# Schematic_traffic.net
KiCad netlist of a schematic drawn in Altium Designer
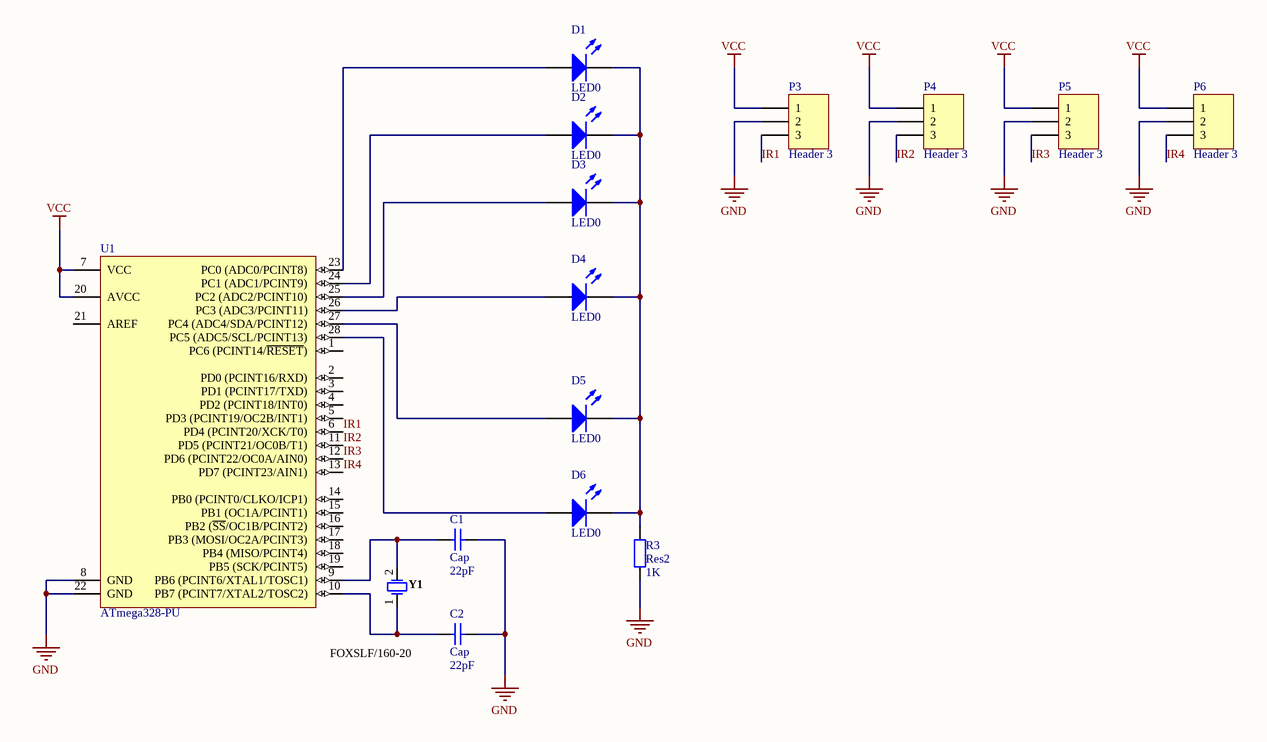
[diagram p0: Schematic_traffic.SchDoc]

(export (version "E")
  (design (tool "Eeschema 10.0.6"))
  (components
    (comp (ref "C1")
      (value "Cap")
      (footprint "RAD-0.3")
      (description "Capacitor")
      (fields (field (name "ALTIUM_VALUE") "22pF") (field (name "PUBLISHER") "Altium Limited"))
      (libsource (lib "Miscellaneous Devices") (part "Cap"))
    )
    (comp (ref "C2")
      (value "Cap")
      (footprint "RAD-0.3")
      (description "Capacitor")
      (fields (field (name "ALTIUM_VALUE") "22pF") (field (name "PUBLISHER") "Altium Limited"))
      (libsource (lib "Miscellaneous Devices") (part "Cap"))
    )
    (comp (ref "D1")
      (value "LED0")
      (footprint "LED-0")
      (description "Typical INFRARED GaAs LED")
      (fields (field (name "PUBLISHER") "Altium Limited"))
      (libsource (lib "Miscellaneous Devices") (part "LED0"))
    )
    (comp (ref "D2")
      (value "LED0")
      (footprint "LED-0")
      (description "Typical INFRARED GaAs LED")
      (fields (field (name "PUBLISHER") "Altium Limited"))
      (libsource (lib "Miscellaneous Devices") (part "LED0"))
    )
    (comp (ref "D3")
      (value "LED0")
      (footprint "LED-0")
      (description "Typical INFRARED GaAs LED")
      (fields (field (name "PUBLISHER") "Altium Limited"))
      (libsource (lib "Miscellaneous Devices") (part "LED0"))
    )
    (comp (ref "D4")
      (value "LED0")
      (footprint "LED-0")
      (description "Typical INFRARED GaAs LED")
      (fields (field (name "PUBLISHER") "Altium Limited"))
      (libsource (lib "Miscellaneous Devices") (part "LED0"))
    )
    (comp (ref "D5")
      (value "LED0")
      (footprint "LED-0")
      (description "Typical INFRARED GaAs LED")
      (fields (field (name "PUBLISHER") "Altium Limited"))
      (libsource (lib "Miscellaneous Devices") (part "LED0"))
    )
    (comp (ref "D6")
      (value "LED0")
      (footprint "LED-0")
      (description "Typical INFRARED GaAs LED")
      (fields (field (name "PUBLISHER") "Altium Limited"))
      (libsource (lib "Miscellaneous Devices") (part "LED0"))
    )
    (comp (ref "P3")
      (value "Header 3")
      (footprint "HDR1X3")
      (description "Header, 3-Pin")
      (fields (field (name "PUBLISHER") "Altium Limited"))
      (libsource (lib "Miscellaneous Connectors") (part "Header 3"))
    )
    (comp (ref "P4")
      (value "Header 3")
      (footprint "HDR1X3")
      (description "Header, 3-Pin")
      (fields (field (name "PUBLISHER") "Altium Limited"))
      (libsource (lib "Miscellaneous Connectors") (part "Header 3"))
    )
    (comp (ref "P5")
      (value "Header 3")
      (footprint "HDR1X3")
      (description "Header, 3-Pin")
      (fields (field (name "PUBLISHER") "Altium Limited"))
      (libsource (lib "Miscellaneous Connectors") (part "Header 3"))
    )
    (comp (ref "P6")
      (value "Header 3")
      (footprint "HDR1X3")
      (description "Header, 3-Pin")
      (fields (field (name "PUBLISHER") "Altium Limited"))
      (libsource (lib "Miscellaneous Connectors") (part "Header 3"))
    )
    (comp (ref "R3")
      (value "Res2")
      (footprint "AXIAL-0.4")
      (description "Resistor")
      (fields (field (name "ALTIUM_VALUE") "1K") (field (name "PUBLISHER") "Altium Limited"))
      (libsource (lib "Miscellaneous Devices") (part "Res2"))
    )
    (comp (ref "U1")
      (value "ATmega328-PU")
      (footprint "28P3")
      (libsource (lib "Altium Content Vault") (part "MC-8B-ATM48-IL28"))
    )
    (comp (ref "Y1")
      (value "FOXSLF/160-20")
      (footprint "FOX-FOXSLF160-20")
      (description "Resistance Weld Thru-Hole Crystal, 16 MHz, -20 to 70 degC, 2-Pin THD, RoHS, Bulk")
      (fields (field (name "TOLERANCE") "1%"))
      (libsource (lib "Altium Content Vault") (part "XTAL-1-2-2"))
    )
  )
  (nets
    (net (code "1") (name "/IR1") (class "Default")
      (node (ref "P3") (pin "3") (pinfunction "3_3") (pintype "passive"))
      (node (ref "U1") (pin "6") (pinfunction "PD4_(PCINT20/XCK/T0)_6") (pintype "bidirectional"))
    )
    (net (code "2") (name "/IR2") (class "Default")
      (node (ref "P4") (pin "3") (pinfunction "3_3") (pintype "passive"))
      (node (ref "U1") (pin "11") (pinfunction "PD5_(PCINT21/OC0B/T1)_11") (pintype "bidirectional"))
    )
    (net (code "3") (name "/IR3") (class "Default")
      (node (ref "P5") (pin "3") (pinfunction "3_3") (pintype "passive"))
      (node (ref "U1") (pin "12") (pinfunction "PD6_(PCINT22/OC0A/AIN0)_12") (pintype "bidirectional"))
    )
    (net (code "4") (name "/IR4") (class "Default")
      (node (ref "P6") (pin "3") (pinfunction "3_3") (pintype "passive"))
      (node (ref "U1") (pin "13") (pinfunction "PD7_(PCINT23/AIN1)_13") (pintype "bidirectional"))
    )
    (net (code "5") (name "GND") (class "Default")
      (node (ref "C1") (pin "1") (pinfunction "1_1") (pintype "passive"))
      (node (ref "C2") (pin "1") (pinfunction "1_1") (pintype "passive"))
      (node (ref "P3") (pin "2") (pinfunction "2_2") (pintype "passive"))
      (node (ref "P4") (pin "2") (pinfunction "2_2") (pintype "passive"))
      (node (ref "P5") (pin "2") (pinfunction "2_2") (pintype "passive"))
      (node (ref "P6") (pin "2") (pinfunction "2_2") (pintype "passive"))
      (node (ref "R3") (pin "1") (pinfunction "1_1") (pintype "passive"))
      (node (ref "U1") (pin "22") (pinfunction "GND_22") (pintype "power_in"))
      (node (ref "U1") (pin "8") (pinfunction "GND_8") (pintype "power_in"))
    )
    (net (code "6") (name "Net-(D1-A)") (class "Default")
      (node (ref "D1") (pin "1") (pinfunction "A_1") (pintype "passive"))
      (node (ref "U1") (pin "23") (pinfunction "PC0_(ADC0/PCINT8)_23") (pintype "bidirectional"))
    )
    (net (code "7") (name "Net-(D1-K)") (class "Default")
      (node (ref "D1") (pin "2") (pinfunction "K_2") (pintype "passive"))
      (node (ref "D2") (pin "2") (pinfunction "K_2") (pintype "passive"))
      (node (ref "D3") (pin "2") (pinfunction "K_2") (pintype "passive"))
      (node (ref "D4") (pin "2") (pinfunction "K_2") (pintype "passive"))
      (node (ref "D5") (pin "2") (pinfunction "K_2") (pintype "passive"))
      (node (ref "D6") (pin "2") (pinfunction "K_2") (pintype "passive"))
      (node (ref "R3") (pin "2") (pinfunction "2_2") (pintype "passive"))
    )
    (net (code "8") (name "Net-(D2-A)") (class "Default")
      (node (ref "D2") (pin "1") (pinfunction "A_1") (pintype "passive"))
      (node (ref "U1") (pin "24") (pinfunction "PC1_(ADC1/PCINT9)_24") (pintype "bidirectional"))
    )
    (net (code "9") (name "Net-(D3-A)") (class "Default")
      (node (ref "D3") (pin "1") (pinfunction "A_1") (pintype "passive"))
      (node (ref "U1") (pin "25") (pinfunction "PC2_(ADC2/PCINT10)_25") (pintype "bidirectional"))
    )
    (net (code "10") (name "Net-(D4-A)") (class "Default")
      (node (ref "D4") (pin "1") (pinfunction "A_1") (pintype "passive"))
      (node (ref "U1") (pin "26") (pinfunction "PC3_(ADC3/PCINT11)_26") (pintype "bidirectional"))
    )
    (net (code "11") (name "Net-(D5-A)") (class "Default")
      (node (ref "D5") (pin "1") (pinfunction "A_1") (pintype "passive"))
      (node (ref "U1") (pin "27") (pinfunction "PC4_(ADC4/SDA/PCINT12)_27") (pintype "bidirectional"))
    )
    (net (code "12") (name "Net-(D6-A)") (class "Default")
      (node (ref "D6") (pin "1") (pinfunction "A_1") (pintype "passive"))
      (node (ref "U1") (pin "28") (pinfunction "PC5_(ADC5/SCL/PCINT13)_28") (pintype "bidirectional"))
    )
    (net (code "13") (name "Net-(U1-PB6_(PCINT6{slash}XTAL1{slash}TOSC1))") (class "Default")
      (node (ref "C1") (pin "2") (pinfunction "2_2") (pintype "passive"))
      (node (ref "U1") (pin "9") (pinfunction "PB6_(PCINT6/XTAL1/TOSC1)_9") (pintype "bidirectional"))
      (node (ref "Y1") (pin "2") (pinfunction "2_2") (pintype "passive"))
    )
    (net (code "14") (name "Net-(U1-PB7_(PCINT7{slash}XTAL2{slash}TOSC2))") (class "Default")
      (node (ref "C2") (pin "2") (pinfunction "2_2") (pintype "passive"))
      (node (ref "U1") (pin "10") (pinfunction "PB7_(PCINT7/XTAL2/TOSC2)_10") (pintype "bidirectional"))
      (node (ref "Y1") (pin "1") (pinfunction "1_1") (pintype "passive"))
    )
    (net (code "15") (name "VCC") (class "Default")
      (node (ref "P3") (pin "1") (pinfunction "1_1") (pintype "passive"))
      (node (ref "P4") (pin "1") (pinfunction "1_1") (pintype "passive"))
      (node (ref "P5") (pin "1") (pinfunction "1_1") (pintype "passive"))
      (node (ref "P6") (pin "1") (pinfunction "1_1") (pintype "passive"))
      (node (ref "U1") (pin "20") (pinfunction "AVCC_20") (pintype "power_in"))
      (node (ref "U1") (pin "7") (pinfunction "VCC_7") (pintype "power_in"))
    )
    (net (code "16") (name "unconnected-(U1-AREF-Pad21)") (class "Default")
      (node (ref "U1") (pin "21") (pinfunction "AREF_21") (pintype "power_in"))
    )
    (net (code "17") (name "unconnected-(U1-PB0_(PCINT0{slash}CLKO{slash}ICP1)-Pad14)") (class "Default")
      (node (ref "U1") (pin "14") (pinfunction "PB0_(PCINT0/CLKO/ICP1)_14") (pintype "bidirectional"))
    )
    (net (code "18") (name "unconnected-(U1-PB1_(OC1A{slash}PCINT1)-Pad15)") (class "Default")
      (node (ref "U1") (pin "15") (pinfunction "PB1_(OC1A/PCINT1)_15") (pintype "bidirectional"))
    )
    (net (code "19") (name "unconnected-(U1-PB2_(~{SS}{slash}OC1B{slash}PCINT2)-Pad16)") (class "Default")
      (node (ref "U1") (pin "16") (pinfunction "PB2_(~{SS}/OC1B/PCINT2)_16") (pintype "bidirectional"))
    )
    (net (code "20") (name "unconnected-(U1-PB3_(MOSI{slash}OC2A{slash}PCINT3)-Pad17)") (class "Default")
      (node (ref "U1") (pin "17") (pinfunction "PB3_(MOSI/OC2A/PCINT3)_17") (pintype "bidirectional"))
    )
    (net (code "21") (name "unconnected-(U1-PB4_(MISO{slash}PCINT4)-Pad18)") (class "Default")
      (node (ref "U1") (pin "18") (pinfunction "PB4_(MISO/PCINT4)_18") (pintype "bidirectional"))
    )
    (net (code "22") (name "unconnected-(U1-PB5_(SCK{slash}PCINT5)-Pad19)") (class "Default")
      (node (ref "U1") (pin "19") (pinfunction "PB5_(SCK/PCINT5)_19") (pintype "bidirectional"))
    )
    (net (code "23") (name "unconnected-(U1-PC6_(PCINT14{slash}~{RESET})-Pad1)") (class "Default")
      (node (ref "U1") (pin "1") (pinfunction "PC6_(PCINT14/~{RESET})_1") (pintype "bidirectional"))
    )
    (net (code "24") (name "unconnected-(U1-PD0_(PCINT16{slash}RXD)-Pad2)") (class "Default")
      (node (ref "U1") (pin "2") (pinfunction "PD0_(PCINT16/RXD)_2") (pintype "bidirectional"))
    )
    (net (code "25") (name "unconnected-(U1-PD1_(PCINT17{slash}TXD)-Pad3)") (class "Default")
      (node (ref "U1") (pin "3") (pinfunction "PD1_(PCINT17/TXD)_3") (pintype "bidirectional"))
    )
    (net (code "26") (name "unconnected-(U1-PD2_(PCINT18{slash}INT0)-Pad4)") (class "Default")
      (node (ref "U1") (pin "4") (pinfunction "PD2_(PCINT18/INT0)_4") (pintype "bidirectional"))
    )
    (net (code "27") (name "unconnected-(U1-PD3_(PCINT19{slash}OC2B{slash}INT1)-Pad5)") (class "Default")
      (node (ref "U1") (pin "5") (pinfunction "PD3_(PCINT19/OC2B/INT1)_5") (pintype "bidirectional"))
    )
  )
)
